# ground_station.net
KiCad netlist of a schematic drawn in Altium Designer
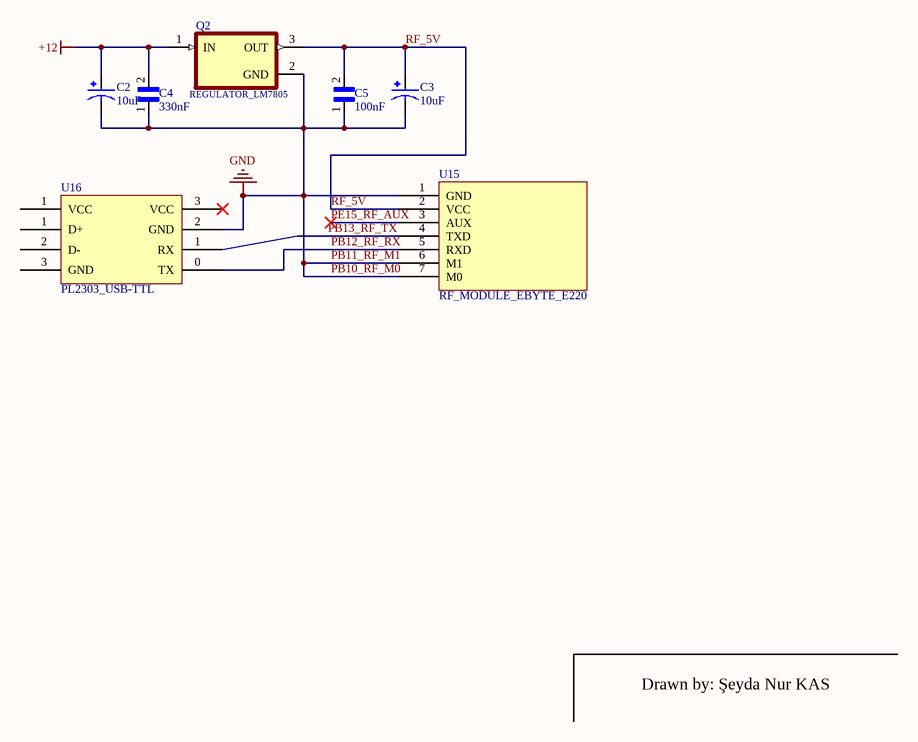
[diagram p0: ground_station.SchDoc]

(export (version "E")
  (design (tool "Eeschema 10.0.6"))
  (components
    (comp (ref "C2")
      (value "10uF")
      (footprint "CAPPRD200W50D500H1500")
      (description "CAP ALUM 10UF 20% 63V RADIAL")
      (fields (field (name "MP") "EEUEB1J100") (field (name "MF") "Panasonic"))
      (libsource (lib "EEUEB1J100") (part "EEUEB1J100"))
    )
    (comp (ref "C3")
      (value "10uF")
      (footprint "CAPPRD200W50D500H1500")
      (description "CAP ALUM 10UF 20% 63V RADIAL")
      (fields (field (name "MP") "EEUEB1J100") (field (name "MF") "Panasonic"))
      (libsource (lib "EEUEB1J100") (part "EEUEB1J100"))
    )
    (comp (ref "C4")
      (value "330nF")
      (footprint "CAPC1608X90N")
      (description "CERAMIC CAPACITOR 16PF 50V, C0G, 5%, 060")
      (fields (field (name "MP") "06035A160JAT2A"))
      (libsource (lib "06035A160JAT2A") (part "06035A160JAT2A"))
    )
    (comp (ref "C5")
      (value "100nF")
      (footprint "CAPC3216X180N")
      (description "Ceramic capacitor SMD 1206 100 nF 50 V 10 % Samsung Electro-Mechanics CL31B104KBCNNNC 4000 pc(s)")
      (fields (field (name "MP") "CL31B104KBCNNNC") (field (name "MF") "Samsung Electro-Mechanics"))
      (libsource (lib "CL31B104KBCNNNC") (part "CL31B104KBCNNNC"))
    )
    (comp (ref "Q2")
      (value "REGULATOR_LM7805")
      (footprint "TO254P1054X470X2600-3")
      (description "Linear Voltage Regulator IC Positive Fixed 1 Output 1.5A TO-220-3")
      (fields (field (name "MF") "ON Semiconductor") (field (name "MP") "LM7805CT"))
      (libsource (lib "LM7805CT_NOPB") (part "LM7805CT/NOPB"))
    )
    (comp (ref "U15") (value "RF_MODULE_EBYTE_E220") (libsource (lib "RF") (part "Component_1")))
    (comp (ref "U16") (value "PL2303_USB-TTL") (libsource (lib "yer") (part "Component_1")))
  )
  (nets
    (net (code "1") (name "+12") (class "Default")
      (node (ref "C2") (pin "P") (pinfunction "P_P") (pintype "passive"))
      (node (ref "C4") (pin "2") (pinfunction "2_2") (pintype "passive"))
      (node (ref "Q2") (pin "1") (pinfunction "IN_1") (pintype "input"))
    )
    (net (code "2") (name "/PB12_RF_RX") (class "Default")
      (node (ref "U15") (pin "5") (pinfunction "RXD_5") (pintype "passive"))
      (node (ref "U16") (pin "0") (pinfunction "TX_0") (pintype "passive"))
    )
    (net (code "3") (name "/PB13_RF_TX") (class "Default")
      (node (ref "U15") (pin "4") (pinfunction "TXD_4") (pintype "passive"))
      (node (ref "U16") (pin "1") (pinfunction "RX_1") (pintype "passive"))
    )
    (net (code "4") (name "/PE15_RF_AUX") (class "Default")
      (node (ref "U15") (pin "3") (pinfunction "AUX_3") (pintype "passive+no_connect"))
    )
    (net (code "5") (name "/RF_5V") (class "Default")
      (node (ref "C3") (pin "P") (pinfunction "P_P") (pintype "passive"))
      (node (ref "C5") (pin "2") (pinfunction "2_2") (pintype "passive"))
      (node (ref "Q2") (pin "3") (pinfunction "OUT_3") (pintype "output"))
      (node (ref "U15") (pin "2") (pinfunction "VCC_2") (pintype "passive"))
    )
    (net (code "6") (name "GND") (class "Default")
      (node (ref "C2") (pin "N") (pinfunction "N_N") (pintype "passive"))
      (node (ref "C3") (pin "N") (pinfunction "N_N") (pintype "passive"))
      (node (ref "C4") (pin "1") (pinfunction "1_1") (pintype "passive"))
      (node (ref "C5") (pin "1") (pinfunction "1_1") (pintype "passive"))
      (node (ref "Q2") (pin "2") (pinfunction "GND_2") (pintype "power_in"))
      (node (ref "U15") (pin "1") (pinfunction "GND_1") (pintype "passive"))
      (node (ref "U15") (pin "6") (pinfunction "M1_6") (pintype "passive"))
      (node (ref "U15") (pin "7") (pinfunction "M0_7") (pintype "passive"))
      (node (ref "U16") (pin "2") (pinfunction "GND_2") (pintype "passive"))
    )
    (net (code "7") (name "unconnected-(U16-D+-Pad1)") (class "Default")
      (node (ref "U16") (pin "1") (pinfunction "D+_1") (pintype "passive"))
    )
    (net (code "8") (name "unconnected-(U16-D--Pad2)") (class "Default")
      (node (ref "U16") (pin "2") (pinfunction "D-_2") (pintype "passive"))
    )
    (net (code "9") (name "unconnected-(U16-GND-Pad3)") (class "Default")
      (node (ref "U16") (pin "3") (pinfunction "GND_3") (pintype "passive"))
    )
    (net (code "10") (name "unconnected-(U16-VCC-Pad1)") (class "Default")
      (node (ref "U16") (pin "1") (pinfunction "VCC_1") (pintype "passive"))
    )
    (net (code "11") (name "unconnected-(U16-VCC-Pad3)") (class "Default")
      (node (ref "U16") (pin "3") (pinfunction "VCC_3") (pintype "passive+no_connect"))
    )
  )
)
